# STC12C5A60S2_DEMO_R1A.net
KiCad netlist of a schematic drawn in Altium Designer
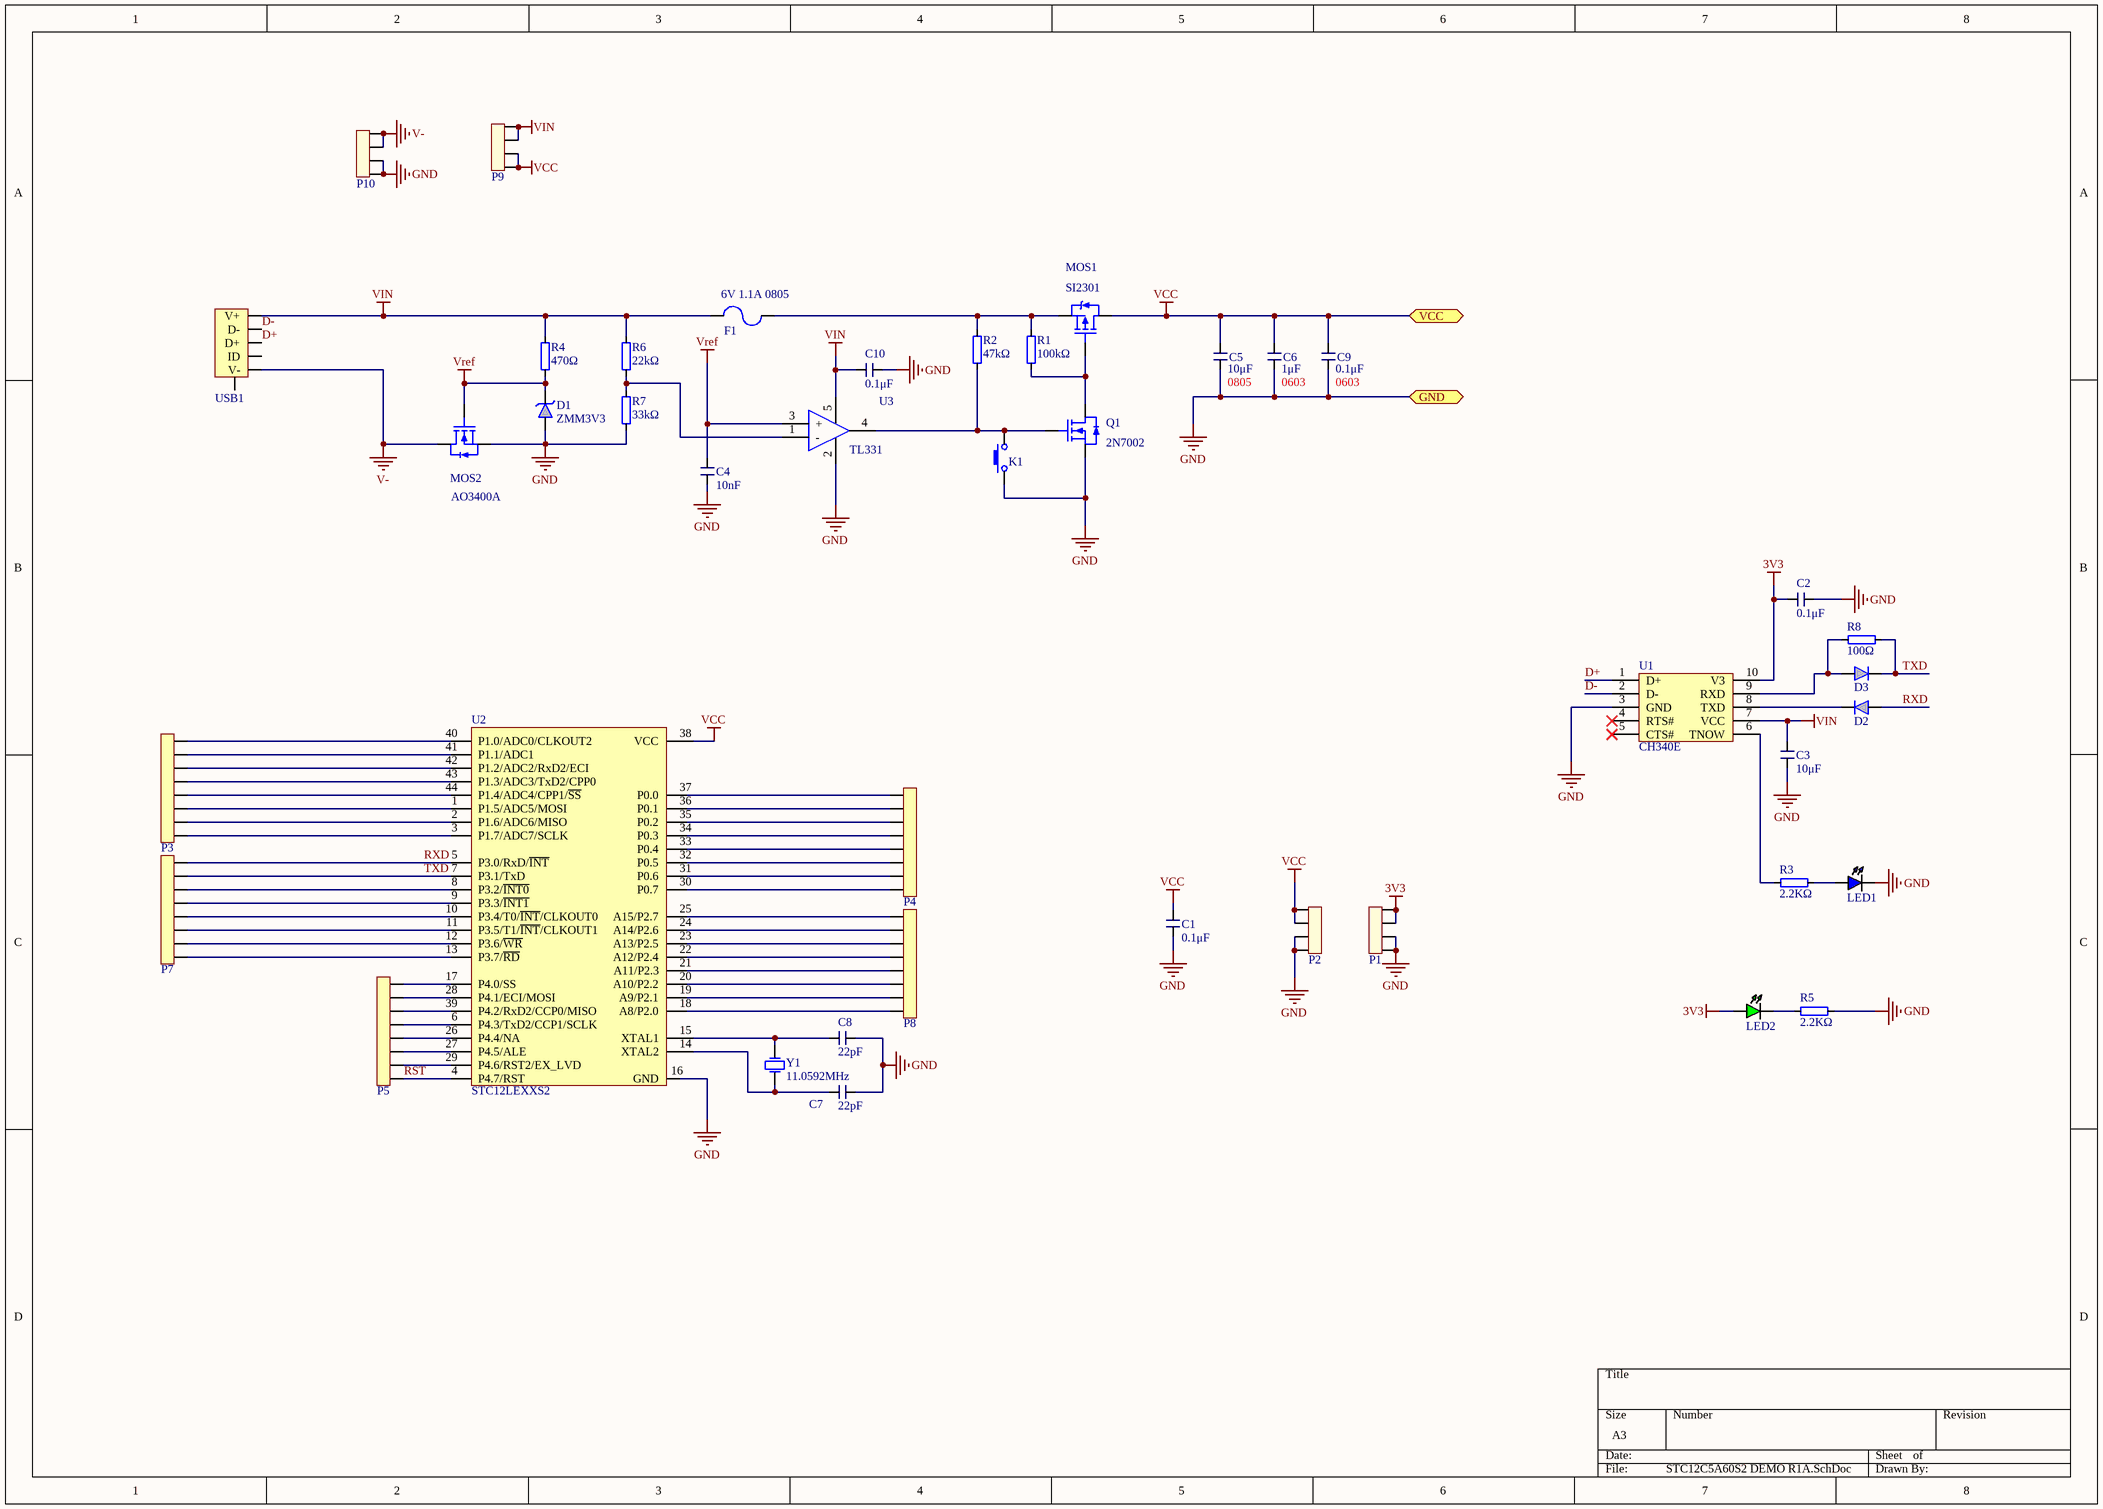
[diagram p0: STC12C5A60S2 DEMO R1A.SchDoc]

(export (version "E")
  (design (tool "Eeschema 10.0.6"))
  (components
    (comp (ref "C1") (value "0.1μF") (footprint "C_0603") (libsource (lib "节能库") (part "C_0603")))
    (comp (ref "C2") (value "0.1μF") (footprint "C_0603") (libsource (lib "节能库") (part "C_0603")))
    (comp (ref "C3") (value "10μF") (footprint "C_0603") (libsource (lib "节能库") (part "C_0603")))
    (comp (ref "C4") (value "10nF") (footprint "C_0603") (libsource (lib "节能库") (part "C_0603")))
    (comp (ref "C5") (value "10μF") (footprint "C_0805") (libsource (lib "节能库") (part "C_0805")))
    (comp (ref "C6") (value "1μF") (footprint "C_0603") (libsource (lib "节能库") (part "C_0603")))
    (comp (ref "C7") (value "22pF") (footprint "C_0603") (libsource (lib "节能库") (part "C_0603")))
    (comp (ref "C8") (value "22pF") (footprint "C_0603") (libsource (lib "节能库") (part "C_0603")))
    (comp (ref "C9") (value "0.1μF") (footprint "C_0603") (libsource (lib "节能库") (part "C_0603")))
    (comp (ref "C10") (value "0.1μF") (footprint "C_0603") (libsource (lib "节能库") (part "C_0603")))
    (comp (ref "D1") (value "ZMM3V3") (footprint "SOD_80") (libsource (lib "节能库") (part "ZMMxxV")))
    (comp (ref "D2") (value "1N4148WS") (footprint "SOD_323") (libsource (lib "节能库") (part "1N4148WS")))
    (comp (ref "D3") (value "1N4148WS") (footprint "SOD_323") (libsource (lib "节能库") (part "1N4148WS")))
    (comp (ref "F1") (value "6V 1.1A 0805") (footprint "FB_0805") (libsource (lib "节能库") (part "FUSE_0805")))
    (comp (ref "K1")
      (value "TACT SWITCH_2_SMD")
      (footprint "TACT SWITCH_2_SMD")
      (libsource (lib "节能库") (part "TACT SWITCH_2_SMD"))
    )
    (comp (ref "LED1")
      (value "LED_0603-B")
      (footprint "LED_0603-B")
      (libsource (lib "节能库") (part "LED_0603-B"))
    )
    (comp (ref "LED2")
      (value "LED_0603-G")
      (footprint "LED_0603-G")
      (libsource (lib "节能库") (part "LED_0603-G"))
    )
    (comp (ref "MOS1") (value "SI2301") (footprint "SOT_23_3") (libsource (lib "节能库") (part "SI2301")))
    (comp (ref "MOS2") (value "AO3400A") (footprint "SOT_23_3") (libsource (lib "节能库") (part "AO3400A")))
    (comp (ref "P1") (value "PIN4") (footprint "PIN_4") (libsource (lib "") (part "PIN4_1")))
    (comp (ref "P2") (value "PIN4") (footprint "PIN_4") (libsource (lib "") (part "PIN4_2")))
    (comp (ref "P3") (value "PIN8") (footprint "PIN_8") (libsource (lib "") (part "PIN8_1")))
    (comp (ref "P4") (value "PIN8") (footprint "PIN_8") (libsource (lib "节能库") (part "PIN8")))
    (comp (ref "P5") (value "PIN8") (footprint "PIN_8") (libsource (lib "") (part "PIN8_1")))
    (comp (ref "P7") (value "PIN8") (footprint "PIN_8") (libsource (lib "") (part "PIN8_1")))
    (comp (ref "P8") (value "PIN8") (footprint "PIN_8") (libsource (lib "节能库") (part "PIN8")))
    (comp (ref "P9") (value "PIN4") (footprint "PIN_4") (libsource (lib "节能库") (part "PIN4")))
    (comp (ref "P10") (value "PIN4") (footprint "PIN_4") (libsource (lib "节能库") (part "PIN4")))
    (comp (ref "Q1") (value "2N7002") (footprint "SOT_23_3") (libsource (lib "节能库") (part "2N7002")))
    (comp (ref "R1") (value "100kΩ") (footprint "R_0603") (libsource (lib "节能库") (part "R_0603")))
    (comp (ref "R2") (value "47kΩ") (footprint "R_0603") (libsource (lib "节能库") (part "R_0603")))
    (comp (ref "R3") (value "2.2KΩ") (footprint "R_0603") (libsource (lib "节能库") (part "R_0603")))
    (comp (ref "R4") (value "470Ω") (footprint "R_0603") (libsource (lib "节能库") (part "R_0603")))
    (comp (ref "R5") (value "2.2KΩ") (footprint "R_0603") (libsource (lib "节能库") (part "R_0603")))
    (comp (ref "R6") (value "22kΩ") (footprint "R_0603") (libsource (lib "节能库") (part "R_0603")))
    (comp (ref "R7") (value "33kΩ") (footprint "R_0603") (libsource (lib "节能库") (part "R_0603")))
    (comp (ref "R8") (value "100Ω") (footprint "R_0603") (libsource (lib "节能库") (part "R_0603")))
    (comp (ref "U1") (value "CH340E") (footprint "MSOP_10") (libsource (lib "节能库") (part "CH340E")))
    (comp (ref "U2")
      (value "STC12LEXXS2")
      (footprint "LQFP_44")
      (libsource (lib "节能库") (part "STC12LE5AXXS2 - LQPF44"))
    )
    (comp (ref "U3") (value "TL331") (footprint "SOT_23_5") (libsource (lib "节能库") (part "TL331")))
    (comp (ref "USB1")
      (value "MICRO USB B")
      (footprint "MICRO USB B")
      (libsource (lib "节能库") (part "MICRO USB B"))
    )
    (comp (ref "Y1")
      (value "11.0592MHz")
      (footprint "Crystal_HC_49US")
      (libsource (lib "节能库") (part "Crystal_HC_49US"))
    )
  )
  (nets
    (net (code "1") (name "/D+") (class "Default")
      (node (ref "U1") (pin "1") (pinfunction "D+_1") (pintype "passive"))
      (node (ref "USB1") (pin "3") (pinfunction "D+_3") (pintype "passive"))
    )
    (net (code "2") (name "/D-") (class "Default")
      (node (ref "U1") (pin "2") (pinfunction "D-_2") (pintype "passive"))
      (node (ref "USB1") (pin "2") (pinfunction "D-_2") (pintype "passive"))
    )
    (net (code "3") (name "/RST") (class "Default")
      (node (ref "P5") (pin "8") (pinfunction "8_8") (pintype "passive"))
      (node (ref "U2") (pin "4") (pinfunction "P4.7/RST_4") (pintype "passive"))
    )
    (net (code "4") (name "/RXD") (class "Default")
      (node (ref "D2") (pin "1") (pinfunction "A_1") (pintype "passive"))
      (node (ref "P7") (pin "1") (pinfunction "1_1") (pintype "passive"))
      (node (ref "U2") (pin "5") (pinfunction "P3.0/RxD/~{INT}_5") (pintype "passive"))
    )
    (net (code "5") (name "/TXD") (class "Default")
      (node (ref "D3") (pin "2") (pinfunction "K_2") (pintype "passive"))
      (node (ref "P7") (pin "2") (pinfunction "2_2") (pintype "passive"))
      (node (ref "R8") (pin "2") (pintype "passive"))
      (node (ref "U2") (pin "7") (pinfunction "P3.1/TxD_7") (pintype "passive"))
    )
    (net (code "6") (name "3V3") (class "Default")
      (node (ref "C2") (pin "2") (pinfunction "2_2") (pintype "passive"))
      (node (ref "LED2") (pin "1") (pinfunction "1_1") (pintype "passive"))
      (node (ref "P1") (pin "3") (pinfunction "3_3") (pintype "passive"))
      (node (ref "P1") (pin "4") (pinfunction "4_4") (pintype "passive"))
      (node (ref "U1") (pin "10") (pinfunction "V3_10") (pintype "passive"))
    )
    (net (code "7") (name "GND") (class "Default")
      (node (ref "C1") (pin "2") (pinfunction "2_2") (pintype "passive"))
      (node (ref "C10") (pin "2") (pinfunction "2_2") (pintype "passive"))
      (node (ref "C2") (pin "1") (pinfunction "1_1") (pintype "passive"))
      (node (ref "C3") (pin "1") (pinfunction "1_1") (pintype "passive"))
      (node (ref "C4") (pin "2") (pinfunction "2_2") (pintype "passive"))
      (node (ref "C5") (pin "2") (pinfunction "2_2") (pintype "passive"))
      (node (ref "C6") (pin "2") (pinfunction "2_2") (pintype "passive"))
      (node (ref "C7") (pin "2") (pinfunction "2_2") (pintype "passive"))
      (node (ref "C8") (pin "2") (pinfunction "2_2") (pintype "passive"))
      (node (ref "C9") (pin "2") (pinfunction "2_2") (pintype "passive"))
      (node (ref "D1") (pin "1") (pinfunction "A_1") (pintype "passive"))
      (node (ref "K1") (pin "1") (pinfunction "1_1") (pintype "passive"))
      (node (ref "LED1") (pin "2") (pinfunction "2_2") (pintype "passive"))
      (node (ref "MOS2") (pin "2") (pinfunction "S_2") (pintype "passive"))
      (node (ref "P1") (pin "1") (pinfunction "1_1") (pintype "passive"))
      (node (ref "P1") (pin "2") (pinfunction "2_2") (pintype "passive"))
      (node (ref "P10") (pin "3") (pinfunction "3_3") (pintype "passive"))
      (node (ref "P10") (pin "4") (pinfunction "4_4") (pintype "passive"))
      (node (ref "P2") (pin "1") (pinfunction "1_1") (pintype "passive"))
      (node (ref "P2") (pin "2") (pinfunction "2_2") (pintype "passive"))
      (node (ref "Q1") (pin "2") (pinfunction "S_2") (pintype "passive"))
      (node (ref "R5") (pin "2") (pintype "passive"))
      (node (ref "R7") (pin "1") (pintype "passive"))
      (node (ref "U1") (pin "3") (pinfunction "GND_3") (pintype "passive"))
      (node (ref "U2") (pin "16") (pinfunction "GND_16") (pintype "passive"))
      (node (ref "U3") (pin "2") (pinfunction "GND_2") (pintype "passive"))
    )
    (net (code "8") (name "Net-(D2-K)") (class "Default")
      (node (ref "D2") (pin "2") (pinfunction "K_2") (pintype "passive"))
      (node (ref "U1") (pin "8") (pinfunction "TXD_8") (pintype "passive"))
    )
    (net (code "9") (name "Net-(D3-A)") (class "Default")
      (node (ref "D3") (pin "1") (pinfunction "A_1") (pintype "passive"))
      (node (ref "R8") (pin "1") (pintype "passive"))
      (node (ref "U1") (pin "9") (pinfunction "RXD_9") (pintype "passive"))
    )
    (net (code "10") (name "Net-(LED1-Pad1)") (class "Default")
      (node (ref "LED1") (pin "1") (pinfunction "1_1") (pintype "passive"))
      (node (ref "R3") (pin "2") (pintype "passive"))
    )
    (net (code "11") (name "Net-(LED2-Pad2)") (class "Default")
      (node (ref "LED2") (pin "2") (pinfunction "2_2") (pintype "passive"))
      (node (ref "R5") (pin "1") (pintype "passive"))
    )
    (net (code "12") (name "Net-(MOS1-G)") (class "Default")
      (node (ref "MOS1") (pin "1") (pinfunction "G_1") (pintype "passive"))
      (node (ref "Q1") (pin "3") (pinfunction "D_3") (pintype "passive"))
      (node (ref "R1") (pin "1") (pintype "passive"))
    )
    (net (code "13") (name "Net-(MOS1-S)") (class "Default")
      (node (ref "F1") (pin "2") (pinfunction "2_2") (pintype "passive"))
      (node (ref "MOS1") (pin "2") (pinfunction "S_2") (pintype "passive"))
      (node (ref "R1") (pin "2") (pintype "passive"))
      (node (ref "R2") (pin "2") (pintype "passive"))
    )
    (net (code "14") (name "Net-(Q1-G)") (class "Default")
      (node (ref "K1") (pin "2") (pinfunction "2_2") (pintype "passive"))
      (node (ref "Q1") (pin "1") (pinfunction "G_1") (pintype "passive"))
      (node (ref "R2") (pin "1") (pintype "passive"))
      (node (ref "U3") (pin "4") (pinfunction "OUT_4") (pintype "passive"))
    )
    (net (code "15") (name "Net-(U1-TNOW)") (class "Default")
      (node (ref "R3") (pin "1") (pintype "passive"))
      (node (ref "U1") (pin "6") (pinfunction "TNOW_6") (pintype "passive"))
    )
    (net (code "16") (name "Net-(U2-A8{slash}P2.0)") (class "Default")
      (node (ref "P8") (pin "1") (pinfunction "1_1") (pintype "passive"))
      (node (ref "U2") (pin "18") (pinfunction "A8/P2.0_18") (pintype "passive"))
    )
    (net (code "17") (name "Net-(U2-A9{slash}P2.1)") (class "Default")
      (node (ref "P8") (pin "2") (pinfunction "2_2") (pintype "passive"))
      (node (ref "U2") (pin "19") (pinfunction "A9/P2.1_19") (pintype "passive"))
    )
    (net (code "18") (name "Net-(U2-A10{slash}P2.2)") (class "Default")
      (node (ref "P8") (pin "3") (pinfunction "3_3") (pintype "passive"))
      (node (ref "U2") (pin "20") (pinfunction "A10/P2.2_20") (pintype "passive"))
    )
    (net (code "19") (name "Net-(U2-A11{slash}P2.3)") (class "Default")
      (node (ref "P8") (pin "4") (pinfunction "4_4") (pintype "passive"))
      (node (ref "U2") (pin "21") (pinfunction "A11/P2.3_21") (pintype "passive"))
    )
    (net (code "20") (name "Net-(U2-A12{slash}P2.4)") (class "Default")
      (node (ref "P8") (pin "5") (pinfunction "5_5") (pintype "passive"))
      (node (ref "U2") (pin "22") (pinfunction "A12/P2.4_22") (pintype "passive"))
    )
    (net (code "21") (name "Net-(U2-A13{slash}P2.5)") (class "Default")
      (node (ref "P8") (pin "6") (pinfunction "6_6") (pintype "passive"))
      (node (ref "U2") (pin "23") (pinfunction "A13/P2.5_23") (pintype "passive"))
    )
    (net (code "22") (name "Net-(U2-A14{slash}P2.6)") (class "Default")
      (node (ref "P8") (pin "7") (pinfunction "7_7") (pintype "passive"))
      (node (ref "U2") (pin "24") (pinfunction "A14/P2.6_24") (pintype "passive"))
    )
    (net (code "23") (name "Net-(U2-A15{slash}P2.7)") (class "Default")
      (node (ref "P8") (pin "8") (pinfunction "8_8") (pintype "passive"))
      (node (ref "U2") (pin "25") (pinfunction "A15/P2.7_25") (pintype "passive"))
    )
    (net (code "24") (name "Net-(U2-P0.0)") (class "Default")
      (node (ref "P4") (pin "8") (pinfunction "8_8") (pintype "passive"))
      (node (ref "U2") (pin "37") (pinfunction "P0.0_37") (pintype "passive"))
    )
    (net (code "25") (name "Net-(U2-P0.1)") (class "Default")
      (node (ref "P4") (pin "7") (pinfunction "7_7") (pintype "passive"))
      (node (ref "U2") (pin "36") (pinfunction "P0.1_36") (pintype "passive"))
    )
    (net (code "26") (name "Net-(U2-P0.2)") (class "Default")
      (node (ref "P4") (pin "6") (pinfunction "6_6") (pintype "passive"))
      (node (ref "U2") (pin "35") (pinfunction "P0.2_35") (pintype "passive"))
    )
    (net (code "27") (name "Net-(U2-P0.3)") (class "Default")
      (node (ref "P4") (pin "5") (pinfunction "5_5") (pintype "passive"))
      (node (ref "U2") (pin "34") (pinfunction "P0.3_34") (pintype "passive"))
    )
    (net (code "28") (name "Net-(U2-P0.4)") (class "Default")
      (node (ref "P4") (pin "4") (pinfunction "4_4") (pintype "passive"))
      (node (ref "U2") (pin "33") (pinfunction "P0.4_33") (pintype "passive"))
    )
    (net (code "29") (name "Net-(U2-P0.5)") (class "Default")
      (node (ref "P4") (pin "3") (pinfunction "3_3") (pintype "passive"))
      (node (ref "U2") (pin "32") (pinfunction "P0.5_32") (pintype "passive"))
    )
    (net (code "30") (name "Net-(U2-P0.6)") (class "Default")
      (node (ref "P4") (pin "2") (pinfunction "2_2") (pintype "passive"))
      (node (ref "U2") (pin "31") (pinfunction "P0.6_31") (pintype "passive"))
    )
    (net (code "31") (name "Net-(U2-P0.7)") (class "Default")
      (node (ref "P4") (pin "1") (pinfunction "1_1") (pintype "passive"))
      (node (ref "U2") (pin "30") (pinfunction "P0.7_30") (pintype "passive"))
    )
    (net (code "32") (name "Net-(U2-P1.0{slash}ADC0{slash}CLKOUT2)") (class "Default")
      (node (ref "P3") (pin "1") (pinfunction "1_1") (pintype "passive"))
      (node (ref "U2") (pin "40") (pinfunction "P1.0/ADC0/CLKOUT2_40") (pintype "passive"))
    )
    (net (code "33") (name "Net-(U2-P1.1{slash}ADC1)") (class "Default")
      (node (ref "P3") (pin "2") (pinfunction "2_2") (pintype "passive"))
      (node (ref "U2") (pin "41") (pinfunction "P1.1/ADC1_41") (pintype "passive"))
    )
    (net (code "34") (name "Net-(U2-P1.2{slash}ADC2{slash}RxD2{slash}ECI)") (class "Default")
      (node (ref "P3") (pin "3") (pinfunction "3_3") (pintype "passive"))
      (node (ref "U2") (pin "42") (pinfunction "P1.2/ADC2/RxD2/ECI_42") (pintype "passive"))
    )
    (net (code "35") (name "Net-(U2-P1.3{slash}ADC3{slash}TxD2{slash}CPP0)") (class "Default")
      (node (ref "P3") (pin "4") (pinfunction "4_4") (pintype "passive"))
      (node (ref "U2") (pin "43") (pinfunction "P1.3/ADC3/TxD2/CPP0_43") (pintype "passive"))
    )
    (net (code "36") (name "Net-(U2-P1.4{slash}ADC4{slash}CPP1{slash}~{SS})") (class "Default")
      (node (ref "P3") (pin "5") (pinfunction "5_5") (pintype "passive"))
      (node (ref "U2") (pin "44") (pinfunction "P1.4/ADC4/CPP1/~{SS}_44") (pintype "passive"))
    )
    (net (code "37") (name "Net-(U2-P1.5{slash}ADC5{slash}MOSI)") (class "Default")
      (node (ref "P3") (pin "6") (pinfunction "6_6") (pintype "passive"))
      (node (ref "U2") (pin "1") (pinfunction "P1.5/ADC5/MOSI_1") (pintype "passive"))
    )
    (net (code "38") (name "Net-(U2-P1.6{slash}ADC6{slash}MISO)") (class "Default")
      (node (ref "P3") (pin "7") (pinfunction "7_7") (pintype "passive"))
      (node (ref "U2") (pin "2") (pinfunction "P1.6/ADC6/MISO_2") (pintype "passive"))
    )
    (net (code "39") (name "Net-(U2-P1.7{slash}ADC7{slash}SCLK)") (class "Default")
      (node (ref "P3") (pin "8") (pinfunction "8_8") (pintype "passive"))
      (node (ref "U2") (pin "3") (pinfunction "P1.7/ADC7/SCLK_3") (pintype "passive"))
    )
    (net (code "40") (name "Net-(U2-P3.2{slash}~{INT0})") (class "Default")
      (node (ref "P7") (pin "3") (pinfunction "3_3") (pintype "passive"))
      (node (ref "U2") (pin "8") (pinfunction "P3.2/~{INT0}_8") (pintype "passive"))
    )
    (net (code "41") (name "Net-(U2-P3.3{slash}~{INT1})") (class "Default")
      (node (ref "P7") (pin "4") (pinfunction "4_4") (pintype "passive"))
      (node (ref "U2") (pin "9") (pinfunction "P3.3/~{INT1}_9") (pintype "passive"))
    )
    (net (code "42") (name "Net-(U2-P3.4{slash}T0{slash}~{INT}{slash}CLKOUT0)") (class "Default")
      (node (ref "P7") (pin "5") (pinfunction "5_5") (pintype "passive"))
      (node (ref "U2") (pin "10") (pinfunction "P3.4/T0/~{INT}/CLKOUT0_10") (pintype "passive"))
    )
    (net (code "43") (name "Net-(U2-P3.5{slash}T1{slash}~{INT}{slash}CLKOUT1)") (class "Default")
      (node (ref "P7") (pin "6") (pinfunction "6_6") (pintype "passive"))
      (node (ref "U2") (pin "11") (pinfunction "P3.5/T1/~{INT}/CLKOUT1_11") (pintype "passive"))
    )
    (net (code "44") (name "Net-(U2-P3.6{slash}~{WR})") (class "Default")
      (node (ref "P7") (pin "7") (pinfunction "7_7") (pintype "passive"))
      (node (ref "U2") (pin "12") (pinfunction "P3.6/~{WR}_12") (pintype "passive"))
    )
    (net (code "45") (name "Net-(U2-P3.7{slash}~{RD})") (class "Default")
      (node (ref "P7") (pin "8") (pinfunction "8_8") (pintype "passive"))
      (node (ref "U2") (pin "13") (pinfunction "P3.7/~{RD}_13") (pintype "passive"))
    )
    (net (code "46") (name "Net-(U2-P4.0{slash}SS)") (class "Default")
      (node (ref "P5") (pin "1") (pinfunction "1_1") (pintype "passive"))
      (node (ref "U2") (pin "17") (pinfunction "P4.0/SS_17") (pintype "passive"))
    )
    (net (code "47") (name "Net-(U2-P4.1{slash}ECI{slash}MOSI)") (class "Default")
      (node (ref "P5") (pin "2") (pinfunction "2_2") (pintype "passive"))
      (node (ref "U2") (pin "28") (pinfunction "P4.1/ECI/MOSI_28") (pintype "passive"))
    )
    (net (code "48") (name "Net-(U2-P4.2{slash}RxD2{slash}CCP0{slash}MISO)") (class "Default")
      (node (ref "P5") (pin "3") (pinfunction "3_3") (pintype "passive"))
      (node (ref "U2") (pin "39") (pinfunction "P4.2/RxD2/CCP0/MISO_39") (pintype "passive"))
    )
    (net (code "49") (name "Net-(U2-P4.3{slash}TxD2{slash}CCP1{slash}SCLK)") (class "Default")
      (node (ref "P5") (pin "4") (pinfunction "4_4") (pintype "passive"))
      (node (ref "U2") (pin "6") (pinfunction "P4.3/TxD2/CCP1/SCLK_6") (pintype "passive"))
    )
    (net (code "50") (name "Net-(U2-P4.4{slash}NA)") (class "Default")
      (node (ref "P5") (pin "5") (pinfunction "5_5") (pintype "passive"))
      (node (ref "U2") (pin "26") (pinfunction "P4.4/NA_26") (pintype "passive"))
    )
    (net (code "51") (name "Net-(U2-P4.5{slash}ALE)") (class "Default")
      (node (ref "P5") (pin "6") (pinfunction "6_6") (pintype "passive"))
      (node (ref "U2") (pin "27") (pinfunction "P4.5/ALE_27") (pintype "passive"))
    )
    (net (code "52") (name "Net-(U2-P4.6{slash}RST2{slash}EX_LVD)") (class "Default")
      (node (ref "P5") (pin "7") (pinfunction "7_7") (pintype "passive"))
      (node (ref "U2") (pin "29") (pinfunction "P4.6/RST2/EX_LVD_29") (pintype "passive"))
    )
    (net (code "53") (name "Net-(U2-XTAL1)") (class "Default")
      (node (ref "C8") (pin "1") (pinfunction "1_1") (pintype "passive"))
      (node (ref "U2") (pin "15") (pinfunction "XTAL1_15") (pintype "passive"))
      (node (ref "Y1") (pin "2") (pinfunction "OSC2_2") (pintype "passive"))
    )
    (net (code "54") (name "Net-(U2-XTAL2)") (class "Default")
      (node (ref "C7") (pin "1") (pinfunction "1_1") (pintype "passive"))
      (node (ref "U2") (pin "14") (pinfunction "XTAL2_14") (pintype "passive"))
      (node (ref "Y1") (pin "1") (pinfunction "OSC1_1") (pintype "passive"))
    )
    (net (code "55") (name "Net-(U3--)") (class "Default")
      (node (ref "R6") (pin "1") (pintype "passive"))
      (node (ref "R7") (pin "2") (pintype "passive"))
      (node (ref "U3") (pin "1") (pinfunction "-_1") (pintype "passive"))
    )
    (net (code "56") (name "V-") (class "Default")
      (node (ref "MOS2") (pin "3") (pinfunction "D_3") (pintype "passive"))
      (node (ref "P10") (pin "1") (pinfunction "1_1") (pintype "passive"))
      (node (ref "P10") (pin "2") (pinfunction "2_2") (pintype "passive"))
      (node (ref "USB1") (pin "5") (pinfunction "V-_5") (pintype "passive"))
    )
    (net (code "57") (name "VCC") (class "Default")
      (node (ref "C1") (pin "1") (pinfunction "1_1") (pintype "passive"))
      (node (ref "C5") (pin "1") (pinfunction "1_1") (pintype "passive"))
      (node (ref "C6") (pin "1") (pinfunction "1_1") (pintype "passive"))
      (node (ref "C9") (pin "1") (pinfunction "1_1") (pintype "passive"))
      (node (ref "MOS1") (pin "3") (pinfunction "D_3") (pintype "passive"))
      (node (ref "P2") (pin "3") (pinfunction "3_3") (pintype "passive"))
      (node (ref "P2") (pin "4") (pinfunction "4_4") (pintype "passive"))
      (node (ref "P9") (pin "3") (pinfunction "3_3") (pintype "passive"))
      (node (ref "P9") (pin "4") (pinfunction "4_4") (pintype "passive"))
      (node (ref "U2") (pin "38") (pinfunction "VCC_38") (pintype "passive"))
    )
    (net (code "58") (name "VIN") (class "Default")
      (node (ref "C10") (pin "1") (pinfunction "1_1") (pintype "passive"))
      (node (ref "C3") (pin "2") (pinfunction "2_2") (pintype "passive"))
      (node (ref "F1") (pin "1") (pinfunction "1_1") (pintype "passive"))
      (node (ref "P9") (pin "1") (pinfunction "1_1") (pintype "passive"))
      (node (ref "P9") (pin "2") (pinfunction "2_2") (pintype "passive"))
      (node (ref "R4") (pin "2") (pintype "passive"))
      (node (ref "R6") (pin "2") (pintype "passive"))
      (node (ref "U1") (pin "7") (pinfunction "VCC_7") (pintype "passive"))
      (node (ref "U3") (pin "5") (pinfunction "VCC_5") (pintype "passive"))
      (node (ref "USB1") (pin "1") (pinfunction "V+_1") (pintype "passive"))
    )
    (net (code "59") (name "Vref") (class "Default")
      (node (ref "C4") (pin "1") (pinfunction "1_1") (pintype "passive"))
      (node (ref "D1") (pin "2") (pinfunction "K_2") (pintype "passive"))
      (node (ref "MOS2") (pin "1") (pinfunction "G_1") (pintype "passive"))
      (node (ref "R4") (pin "1") (pintype "passive"))
      (node (ref "U3") (pin "3") (pinfunction "+_3") (pintype "passive"))
    )
    (net (code "60") (name "unconnected-(U1-CTS#-Pad5)") (class "Default")
      (node (ref "U1") (pin "5") (pinfunction "CTS#_5") (pintype "passive+no_connect"))
    )
    (net (code "61") (name "unconnected-(U1-RTS#-Pad4)") (class "Default")
      (node (ref "U1") (pin "4") (pinfunction "RTS#_4") (pintype "passive+no_connect"))
    )
    (net (code "62") (name "unconnected-(USB1-GND-Pad0)") (class "Default")
      (node (ref "USB1") (pin "0") (pinfunction "GND_0") (pintype "passive"))
    )
    (net (code "63") (name "unconnected-(USB1-ID-Pad4)") (class "Default")
      (node (ref "USB1") (pin "4") (pinfunction "ID_4") (pintype "passive"))
    )
  )
)
